# czujniki2.net
KiCad netlist of a schematic drawn in Altium Designer
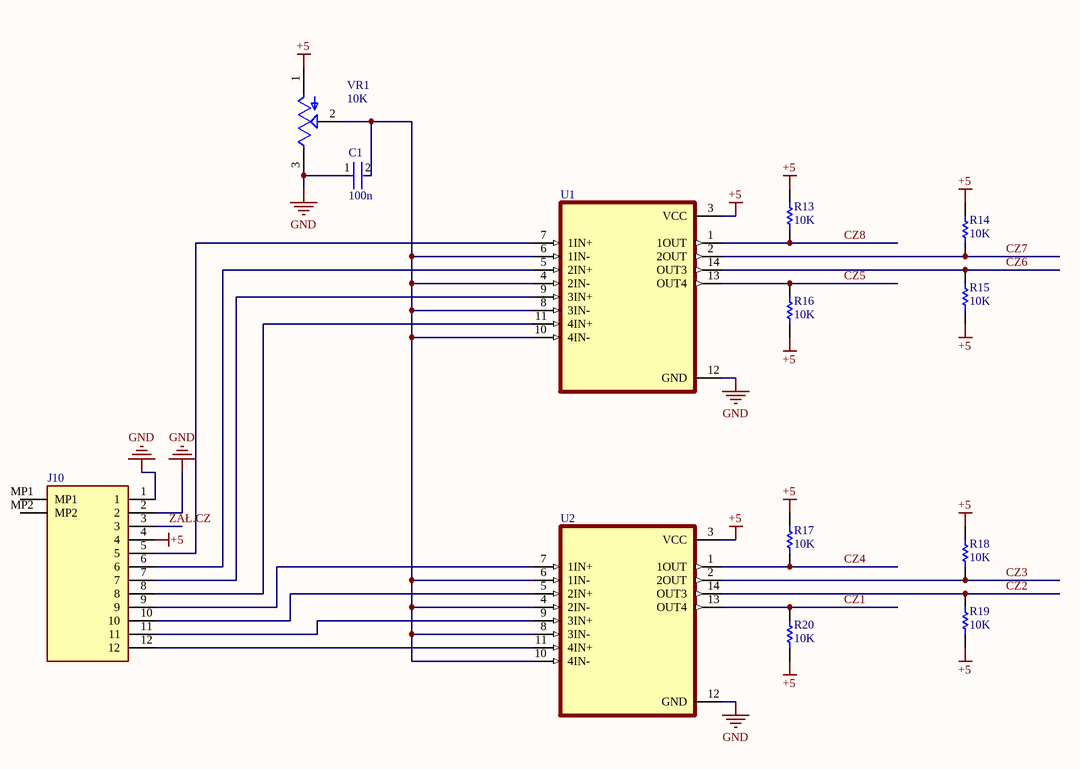
[diagram p0: czujniki2.SchDoc]

(export (version "E")
  (design (tool "Eeschema 10.0.6"))
  (components
    (comp (ref "C1")
      (value "100n")
      (footprint "FP-0805-L_2_01_0_2-W_1_25-IPC_B")
      (description "General Purpose Ceramic Capacitor, 0805, 100nF, 10%, X7R, 15%, 100V")
      (fields (field (name "VOLTAGE") "100V") (field (name "TOLERANCE") "10%"))
      (libsource (lib "Altium Content Vault") (part "b4654b650e69147ec39a6b967a45e02"))
    )
    (comp (ref "J10")
      (value "AFA07-S12FCA-00")
      (footprint "AFA07S12FCA00")
      (description "FFC, FPC Connectors P=1mm RoHS")
      (libsource (lib "AFA07-S12FCA-00") (part "AFA07-S12FCA-00"))
    )
    (comp (ref "R13")
      (value "10K")
      (footprint "RESC2013X60X35NL10T20")
      (description "Chip Resistor, 10 KOhm, +/- 1%, 0.125 W, -55 to 155 degC, 0805 (2012 Metric), RoHS, Tape and Reel")
      (fields (field (name "MANUFACTURER") "Yageo"))
      (libsource (lib "Altium Content Vault") (part "RES-2"))
    )
    (comp (ref "R14")
      (value "10K")
      (footprint "RESC2013X60X35NL10T20")
      (description "Chip Resistor, 10 KOhm, +/- 1%, 0.125 W, -55 to 155 degC, 0805 (2012 Metric), RoHS, Tape and Reel")
      (fields (field (name "MANUFACTURER") "Yageo"))
      (libsource (lib "Altium Content Vault") (part "RES-2"))
    )
    (comp (ref "R15")
      (value "10K")
      (footprint "RESC2013X60X35NL10T20")
      (description "Chip Resistor, 10 KOhm, +/- 1%, 0.125 W, -55 to 155 degC, 0805 (2012 Metric), RoHS, Tape and Reel")
      (fields (field (name "MANUFACTURER") "Yageo"))
      (libsource (lib "Altium Content Vault") (part "RES-2"))
    )
    (comp (ref "R16")
      (value "10K")
      (footprint "RESC2013X60X35NL10T20")
      (description "Chip Resistor, 10 KOhm, +/- 1%, 0.125 W, -55 to 155 degC, 0805 (2012 Metric), RoHS, Tape and Reel")
      (fields (field (name "MANUFACTURER") "Yageo"))
      (libsource (lib "Altium Content Vault") (part "RES-2"))
    )
    (comp (ref "R17")
      (value "10K")
      (footprint "RESC2013X60X35NL10T20")
      (description "Chip Resistor, 10 KOhm, +/- 1%, 0.125 W, -55 to 155 degC, 0805 (2012 Metric), RoHS, Tape and Reel")
      (fields (field (name "MANUFACTURER") "Yageo"))
      (libsource (lib "Altium Content Vault") (part "RES-2"))
    )
    (comp (ref "R18")
      (value "10K")
      (footprint "RESC2013X60X35NL10T20")
      (description "Chip Resistor, 10 KOhm, +/- 1%, 0.125 W, -55 to 155 degC, 0805 (2012 Metric), RoHS, Tape and Reel")
      (fields (field (name "MANUFACTURER") "Yageo"))
      (libsource (lib "Altium Content Vault") (part "RES-2"))
    )
    (comp (ref "R19")
      (value "10K")
      (footprint "RESC2013X60X35NL10T20")
      (description "Chip Resistor, 10 KOhm, +/- 1%, 0.125 W, -55 to 155 degC, 0805 (2012 Metric), RoHS, Tape and Reel")
      (fields (field (name "MANUFACTURER") "Yageo"))
      (libsource (lib "Altium Content Vault") (part "RES-2"))
    )
    (comp (ref "R20")
      (value "10K")
      (footprint "RESC2013X60X35NL10T20")
      (description "Chip Resistor, 10 KOhm, +/- 1%, 0.125 W, -55 to 155 degC, 0805 (2012 Metric), RoHS, Tape and Reel")
      (fields (field (name "MANUFACTURER") "Yageo"))
      (libsource (lib "Altium Content Vault") (part "RES-2"))
    )
    (comp (ref "U1")
      (value "LM339D")
      (footprint "SOIC127P600X175-14N:SOIC127P600X175-14N")
      (libsource (lib "LM339D") (part "LM339D"))
    )
    (comp (ref "U2")
      (value "LM339D")
      (footprint "SOIC127P600X175-14N:SOIC127P600X175-14N")
      (libsource (lib "LM339D") (part "LM339D"))
    )
    (comp (ref "VR1")
      (value "10K")
      (footprint "TRIM_3362P-1-103")
      (description "10 kOhms 0.5W, 1/2W PC Pins Through Hole Trimmer Potentiometer Cermet 1 Turn Top Adjustment")
      (fields (field (name "MF") "Bourns") (field (name "MP") "3362P-1-103"))
      (libsource (lib "3362P-1-103") (part "3362P-1-103"))
    )
  )
  (nets
    (net (code "1") (name "+5") (class "Default")
      (node (ref "J10") (pin "4") (pinfunction "4_4") (pintype "passive"))
      (node (ref "R13") (pin "2") (pinfunction "2_2") (pintype "passive"))
      (node (ref "R14") (pin "2") (pinfunction "2_2") (pintype "passive"))
      (node (ref "R15") (pin "1") (pinfunction "1_1") (pintype "passive"))
      (node (ref "R16") (pin "1") (pinfunction "1_1") (pintype "passive"))
      (node (ref "R17") (pin "2") (pinfunction "2_2") (pintype "passive"))
      (node (ref "R18") (pin "2") (pinfunction "2_2") (pintype "passive"))
      (node (ref "R19") (pin "1") (pinfunction "1_1") (pintype "passive"))
      (node (ref "R20") (pin "1") (pinfunction "1_1") (pintype "passive"))
      (node (ref "U1") (pin "3") (pinfunction "VCC_3") (pintype "power_in"))
      (node (ref "U2") (pin "3") (pinfunction "VCC_3") (pintype "power_in"))
      (node (ref "VR1") (pin "1") (pinfunction "CCW_1") (pintype "passive"))
    )
    (net (code "2") (name "/CZ1") (class "Default")
      (node (ref "R20") (pin "2") (pinfunction "2_2") (pintype "passive"))
      (node (ref "U2") (pin "13") (pinfunction "OUT4_13") (pintype "output"))
    )
    (net (code "3") (name "/CZ2") (class "Default")
      (node (ref "R19") (pin "2") (pinfunction "2_2") (pintype "passive"))
      (node (ref "U2") (pin "14") (pinfunction "OUT3_14") (pintype "output"))
    )
    (net (code "4") (name "/CZ3") (class "Default")
      (node (ref "R18") (pin "1") (pinfunction "1_1") (pintype "passive"))
      (node (ref "U2") (pin "2") (pinfunction "2OUT_2") (pintype "output"))
    )
    (net (code "5") (name "/CZ4") (class "Default")
      (node (ref "R17") (pin "1") (pinfunction "1_1") (pintype "passive"))
      (node (ref "U2") (pin "1") (pinfunction "1OUT_1") (pintype "output"))
    )
    (net (code "6") (name "/CZ5") (class "Default")
      (node (ref "R16") (pin "2") (pinfunction "2_2") (pintype "passive"))
      (node (ref "U1") (pin "13") (pinfunction "OUT4_13") (pintype "output"))
    )
    (net (code "7") (name "/CZ6") (class "Default")
      (node (ref "R15") (pin "2") (pinfunction "2_2") (pintype "passive"))
      (node (ref "U1") (pin "14") (pinfunction "OUT3_14") (pintype "output"))
    )
    (net (code "8") (name "/CZ7") (class "Default")
      (node (ref "R14") (pin "1") (pinfunction "1_1") (pintype "passive"))
      (node (ref "U1") (pin "2") (pinfunction "2OUT_2") (pintype "output"))
    )
    (net (code "9") (name "/CZ8") (class "Default")
      (node (ref "R13") (pin "1") (pinfunction "1_1") (pintype "passive"))
      (node (ref "U1") (pin "1") (pinfunction "1OUT_1") (pintype "output"))
    )
    (net (code "10") (name "/ZAŁ.CZ") (class "Default")
      (node (ref "J10") (pin "3") (pinfunction "3_3") (pintype "passive"))
    )
    (net (code "11") (name "GND") (class "Default")
      (node (ref "C1") (pin "1") (pinfunction "1_1") (pintype "passive"))
      (node (ref "J10") (pin "1") (pinfunction "1_1") (pintype "passive"))
      (node (ref "J10") (pin "2") (pinfunction "2_2") (pintype "passive"))
      (node (ref "U1") (pin "12") (pinfunction "GND_12") (pintype "power_in"))
      (node (ref "U2") (pin "12") (pinfunction "GND_12") (pintype "power_in"))
      (node (ref "VR1") (pin "3") (pinfunction "CW_3") (pintype "passive"))
    )
    (net (code "12") (name "Net-(U1-1IN+)") (class "Default")
      (node (ref "J10") (pin "5") (pinfunction "5_5") (pintype "passive"))
      (node (ref "U1") (pin "7") (pinfunction "1IN+_7") (pintype "input"))
    )
    (net (code "13") (name "Net-(U1-1IN-)") (class "Default")
      (node (ref "C1") (pin "2") (pinfunction "2_2") (pintype "passive"))
      (node (ref "U1") (pin "10") (pinfunction "4IN-_10") (pintype "input"))
      (node (ref "U1") (pin "4") (pinfunction "2IN-_4") (pintype "input"))
      (node (ref "U1") (pin "6") (pinfunction "1IN-_6") (pintype "input"))
      (node (ref "U1") (pin "8") (pinfunction "3IN-_8") (pintype "input"))
      (node (ref "U2") (pin "10") (pinfunction "4IN-_10") (pintype "input"))
      (node (ref "U2") (pin "4") (pinfunction "2IN-_4") (pintype "input"))
      (node (ref "U2") (pin "6") (pinfunction "1IN-_6") (pintype "input"))
      (node (ref "U2") (pin "8") (pinfunction "3IN-_8") (pintype "input"))
      (node (ref "VR1") (pin "2") (pinfunction "WIPER_2") (pintype "passive"))
    )
    (net (code "14") (name "Net-(U1-2IN+)") (class "Default")
      (node (ref "J10") (pin "6") (pinfunction "6_6") (pintype "passive"))
      (node (ref "U1") (pin "5") (pinfunction "2IN+_5") (pintype "input"))
    )
    (net (code "15") (name "Net-(U1-3IN+)") (class "Default")
      (node (ref "J10") (pin "7") (pinfunction "7_7") (pintype "passive"))
      (node (ref "U1") (pin "9") (pinfunction "3IN+_9") (pintype "input"))
    )
    (net (code "16") (name "Net-(U1-4IN+)") (class "Default")
      (node (ref "J10") (pin "8") (pinfunction "8_8") (pintype "passive"))
      (node (ref "U1") (pin "11") (pinfunction "4IN+_11") (pintype "input"))
    )
    (net (code "17") (name "Net-(U2-1IN+)") (class "Default")
      (node (ref "J10") (pin "9") (pinfunction "9_9") (pintype "passive"))
      (node (ref "U2") (pin "7") (pinfunction "1IN+_7") (pintype "input"))
    )
    (net (code "18") (name "Net-(U2-2IN+)") (class "Default")
      (node (ref "J10") (pin "10") (pinfunction "10_10") (pintype "passive"))
      (node (ref "U2") (pin "5") (pinfunction "2IN+_5") (pintype "input"))
    )
    (net (code "19") (name "Net-(U2-3IN+)") (class "Default")
      (node (ref "J10") (pin "11") (pinfunction "11_11") (pintype "passive"))
      (node (ref "U2") (pin "9") (pinfunction "3IN+_9") (pintype "input"))
    )
    (net (code "20") (name "Net-(U2-4IN+)") (class "Default")
      (node (ref "J10") (pin "12") (pinfunction "12_12") (pintype "passive"))
      (node (ref "U2") (pin "11") (pinfunction "4IN+_11") (pintype "input"))
    )
    (net (code "21") (name "unconnected-(J10-PadMP1)") (class "Default")
      (node (ref "J10") (pin "MP1") (pinfunction "MP1_MP1") (pintype "passive"))
    )
    (net (code "22") (name "unconnected-(J10-PadMP2)") (class "Default")
      (node (ref "J10") (pin "MP2") (pinfunction "MP2_MP2") (pintype "passive"))
    )
  )
)
